# 03_-_SCHEMATIC.net
KiCad netlist of a schematic drawn in Altium Designer
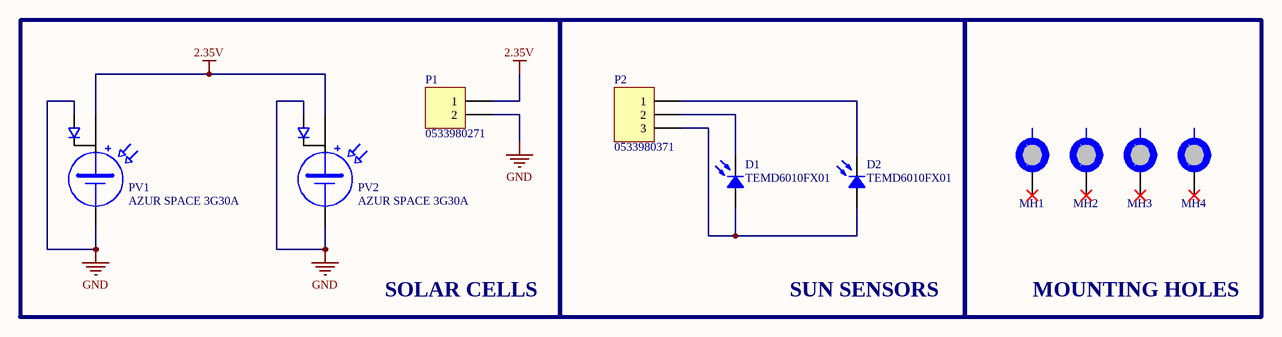
[diagram p0: [03] - SCHEMATIC.SchDoc]

(export (version "E")
  (design (tool "Eeschema 10.0.6"))
  (components
    (comp (ref "D1")
      (value "TEMD6010FX01")
      (footprint "TEMD6010FX01")
      (description "Ambient Light Sensor")
      (fields (field (name "MANUFACTURER") "Vishay Semiconductors"))
      (libsource (lib "UVG") (part "TEMD6010FX01"))
    )
    (comp (ref "D2")
      (value "TEMD6010FX01")
      (footprint "TEMD6010FX01")
      (description "Ambient Light Sensor")
      (fields (field (name "MANUFACTURER") "Vishay Semiconductors"))
      (libsource (lib "UVG") (part "TEMD6010FX01"))
    )
    (comp (ref "MH1")
      (value "MH_3.8MMNC_2.5MMD")
      (footprint "MH_3.8MMNC_2.5MMD_NON_COPPER_NPTH")
      (description "Mounting Hole 3.8mm Diameter (Non Copper), 2.5mm Drill NPTH")
      (libsource (lib "UVG") (part "MH_3.8MMNC_2MMD"))
    )
    (comp (ref "MH2")
      (value "MH_3.8MMNC_2.5MMD")
      (footprint "MH_3.8MMNC_2.5MMD_NON_COPPER_NPTH")
      (description "Mounting Hole 3.8mm Diameter (Non Copper), 2.5mm Drill NPTH")
      (libsource (lib "UVG") (part "MH_3.8MMNC_2MMD"))
    )
    (comp (ref "MH3")
      (value "MH_3.8MMNC_2.5MMD")
      (footprint "MH_3.8MMNC_2.5MMD_NON_COPPER_NPTH")
      (description "Mounting Hole 3.8mm Diameter (Non Copper), 2.5mm Drill NPTH")
      (libsource (lib "UVG") (part "MH_3.8MMNC_2MMD"))
    )
    (comp (ref "MH4")
      (value "MH_3.8MMNC_2.5MMD")
      (footprint "MH_3.8MMNC_2.5MMD_NON_COPPER_NPTH")
      (description "Mounting Hole 3.8mm Diameter (Non Copper), 2.5mm Drill NPTH")
      (libsource (lib "UVG") (part "MH_3.8MMNC_2MMD"))
    )
    (comp (ref "P1")
      (value "0533980271")
      (footprint "0533980271")
      (description "2 Positions Header, Shrouded Connector 0.049\" (1.25mm) Surface Mount, Right Angle Tin")
      (fields (field (name "MANUFACTURER") "Molex"))
      (libsource (lib "UVG") (part "0533980271"))
    )
    (comp (ref "P2")
      (value "0533980371")
      (footprint "0533980371")
      (description "3 Positions Header, Shrouded Connector 0.049\" (1.25mm) Surface Mount Tin")
      (fields (field (name "MANUFACTURER") "Molex"))
      (libsource (lib "UVG") (part "0533980371"))
    )
    (comp (ref "PV1")
      (value "AZUR SPACE 3G30A")
      (footprint "AZUR SPACE 3G30A")
      (description "30% Triple Junction GaAs Solar Cell Assembly")
      (libsource (lib "UVG") (part "AZUR SPACE 3G30A"))
    )
    (comp (ref "PV2")
      (value "AZUR SPACE 3G30A")
      (footprint "AZUR SPACE 3G30A")
      (description "30% Triple Junction GaAs Solar Cell Assembly")
      (libsource (lib "UVG") (part "AZUR SPACE 3G30A"))
    )
  )
  (nets
    (net (code "1") (name "2.35V") (class "Default")
      (node (ref "P1") (pin "1") (pinfunction "1_1") (pintype "passive"))
      (node (ref "PV1") (pin "1") (pinfunction "1_1") (pintype "passive"))
      (node (ref "PV2") (pin "1") (pinfunction "1_1") (pintype "passive"))
    )
    (net (code "2") (name "GND") (class "Default")
      (node (ref "P1") (pin "2") (pinfunction "2_2") (pintype "passive"))
      (node (ref "PV1") (pin "2") (pinfunction "2_2") (pintype "passive"))
      (node (ref "PV1") (pin "3") (pinfunction "3_3") (pintype "passive"))
      (node (ref "PV2") (pin "2") (pinfunction "2_2") (pintype "passive"))
      (node (ref "PV2") (pin "3") (pinfunction "3_3") (pintype "passive"))
    )
    (net (code "3") (name "Net-(D1-Pad1)") (class "Default")
      (node (ref "D1") (pin "1") (pinfunction "1_1") (pintype "passive"))
      (node (ref "D2") (pin "1") (pinfunction "1_1") (pintype "passive"))
      (node (ref "P2") (pin "3") (pinfunction "3_3") (pintype "passive"))
    )
    (net (code "4") (name "Net-(D1-Pad2)") (class "Default")
      (node (ref "D1") (pin "2") (pinfunction "2_2") (pintype "passive"))
      (node (ref "P2") (pin "2") (pinfunction "2_2") (pintype "passive"))
    )
    (net (code "5") (name "Net-(D2-Pad2)") (class "Default")
      (node (ref "D2") (pin "2") (pinfunction "2_2") (pintype "passive"))
      (node (ref "P2") (pin "1") (pinfunction "1_1") (pintype "passive"))
    )
    (net (code "6") (name "unconnected-(MH1-Pad1)") (class "Default")
      (node (ref "MH1") (pin "1") (pinfunction "1_1") (pintype "passive"))
    )
    (net (code "7") (name "unconnected-(MH2-Pad1)") (class "Default")
      (node (ref "MH2") (pin "1") (pinfunction "1_1") (pintype "passive"))
    )
    (net (code "8") (name "unconnected-(MH3-Pad1)") (class "Default")
      (node (ref "MH3") (pin "1") (pinfunction "1_1") (pintype "passive"))
    )
    (net (code "9") (name "unconnected-(MH4-Pad1)") (class "Default")
      (node (ref "MH4") (pin "1") (pinfunction "1_1") (pintype "passive"))
    )
  )
)
